# schema.net
KiCad netlist of a schematic drawn in Altium Designer
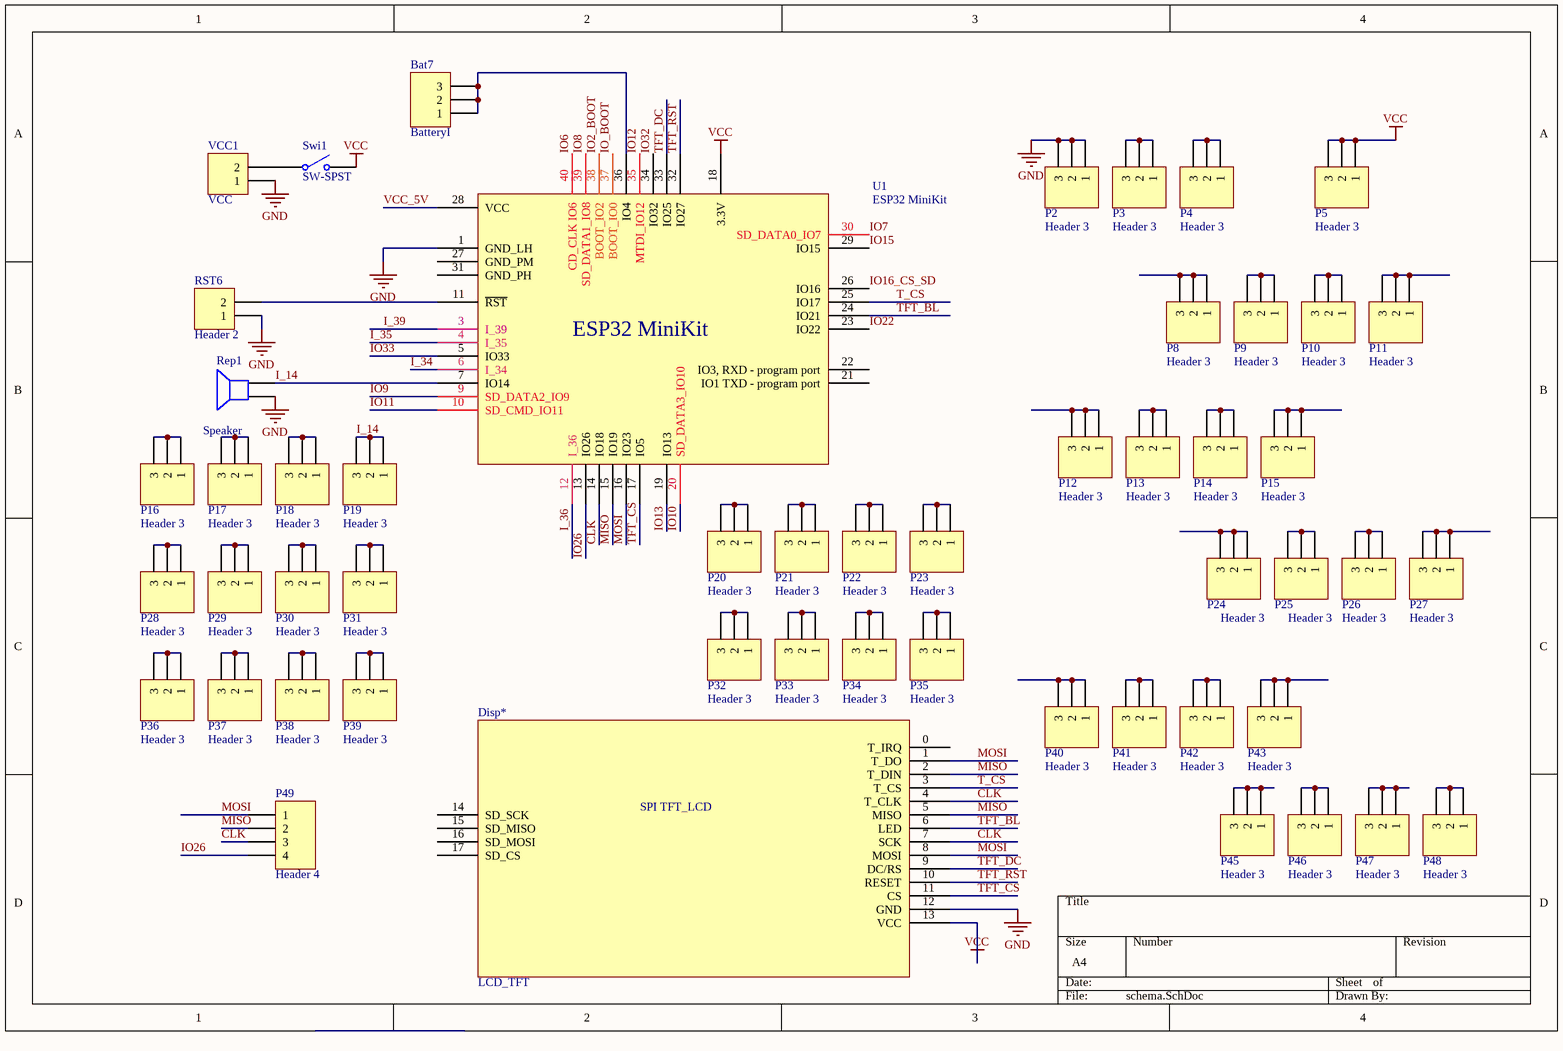
[diagram p0: schema.SchDoc]

(export (version "E")
  (design (tool "Eeschema 10.0.6"))
  (components
    (comp (ref "Bat7")
      (value "BatteryI")
      (footprint "HDR1X3")
      (description "Header, 3-Pin")
      (fields (field (name "PUBLISHER") "Altium Limited"))
      (libsource (lib "") (part "Header 3_1"))
    )
    (comp (ref "Disp*")
      (value "LCD_TFT")
      (footprint "TCT_SPI_480x320 ST7796")
      (libsource (lib "D1_Mini") (part "480x320_tft_SPI_LCD"))
    )
    (comp (ref "P2")
      (value "Header 3")
      (footprint "HDR1X3")
      (description "Header, 3-Pin")
      (fields (field (name "PUBLISHER") "Altium Limited"))
      (libsource (lib "Miscellaneous Connectors") (part "Header 3"))
    )
    (comp (ref "P3")
      (value "Header 3")
      (footprint "HDR1X3")
      (description "Header, 3-Pin")
      (fields (field (name "PUBLISHER") "Altium Limited"))
      (libsource (lib "Miscellaneous Connectors") (part "Header 3"))
    )
    (comp (ref "P4")
      (value "Header 3")
      (footprint "HDR1X3")
      (description "Header, 3-Pin")
      (fields (field (name "PUBLISHER") "Altium Limited"))
      (libsource (lib "Miscellaneous Connectors") (part "Header 3"))
    )
    (comp (ref "P5")
      (value "Header 3")
      (footprint "HDR1X3")
      (description "Header, 3-Pin")
      (fields (field (name "PUBLISHER") "Altium Limited"))
      (libsource (lib "Miscellaneous Connectors") (part "Header 3"))
    )
    (comp (ref "P8")
      (value "Header 3")
      (footprint "HDR1X3")
      (description "Header, 3-Pin")
      (fields (field (name "PUBLISHER") "Altium Limited"))
      (libsource (lib "Miscellaneous Connectors") (part "Header 3"))
    )
    (comp (ref "P9")
      (value "Header 3")
      (footprint "HDR1X3")
      (description "Header, 3-Pin")
      (fields (field (name "PUBLISHER") "Altium Limited"))
      (libsource (lib "Miscellaneous Connectors") (part "Header 3"))
    )
    (comp (ref "P10")
      (value "Header 3")
      (footprint "HDR1X3")
      (description "Header, 3-Pin")
      (fields (field (name "PUBLISHER") "Altium Limited"))
      (libsource (lib "Miscellaneous Connectors") (part "Header 3"))
    )
    (comp (ref "P11")
      (value "Header 3")
      (footprint "HDR1X3")
      (description "Header, 3-Pin")
      (fields (field (name "PUBLISHER") "Altium Limited"))
      (libsource (lib "Miscellaneous Connectors") (part "Header 3"))
    )
    (comp (ref "P12")
      (value "Header 3")
      (footprint "HDR1X3")
      (description "Header, 3-Pin")
      (fields (field (name "PUBLISHER") "Altium Limited"))
      (libsource (lib "Miscellaneous Connectors") (part "Header 3"))
    )
    (comp (ref "P13")
      (value "Header 3")
      (footprint "HDR1X3")
      (description "Header, 3-Pin")
      (fields (field (name "PUBLISHER") "Altium Limited"))
      (libsource (lib "Miscellaneous Connectors") (part "Header 3"))
    )
    (comp (ref "P14")
      (value "Header 3")
      (footprint "HDR1X3")
      (description "Header, 3-Pin")
      (fields (field (name "PUBLISHER") "Altium Limited"))
      (libsource (lib "Miscellaneous Connectors") (part "Header 3"))
    )
    (comp (ref "P15")
      (value "Header 3")
      (footprint "HDR1X3")
      (description "Header, 3-Pin")
      (fields (field (name "PUBLISHER") "Altium Limited"))
      (libsource (lib "Miscellaneous Connectors") (part "Header 3"))
    )
    (comp (ref "P16")
      (value "Header 3")
      (footprint "HDR1X3")
      (description "Header, 3-Pin")
      (fields (field (name "PUBLISHER") "Altium Limited"))
      (libsource (lib "Miscellaneous Connectors") (part "Header 3"))
    )
    (comp (ref "P17")
      (value "Header 3")
      (footprint "HDR1X3")
      (description "Header, 3-Pin")
      (fields (field (name "PUBLISHER") "Altium Limited"))
      (libsource (lib "Miscellaneous Connectors") (part "Header 3"))
    )
    (comp (ref "P18")
      (value "Header 3")
      (footprint "HDR1X3")
      (description "Header, 3-Pin")
      (fields (field (name "PUBLISHER") "Altium Limited"))
      (libsource (lib "Miscellaneous Connectors") (part "Header 3"))
    )
    (comp (ref "P19")
      (value "Header 3")
      (footprint "HDR1X3")
      (description "Header, 3-Pin")
      (fields (field (name "PUBLISHER") "Altium Limited"))
      (libsource (lib "Miscellaneous Connectors") (part "Header 3"))
    )
    (comp (ref "P20")
      (value "Header 3")
      (footprint "HDR1X3")
      (description "Header, 3-Pin")
      (fields (field (name "PUBLISHER") "Altium Limited"))
      (libsource (lib "Miscellaneous Connectors") (part "Header 3"))
    )
    (comp (ref "P21")
      (value "Header 3")
      (footprint "HDR1X3")
      (description "Header, 3-Pin")
      (fields (field (name "PUBLISHER") "Altium Limited"))
      (libsource (lib "Miscellaneous Connectors") (part "Header 3"))
    )
    (comp (ref "P22")
      (value "Header 3")
      (footprint "HDR1X3")
      (description "Header, 3-Pin")
      (fields (field (name "PUBLISHER") "Altium Limited"))
      (libsource (lib "Miscellaneous Connectors") (part "Header 3"))
    )
    (comp (ref "P23")
      (value "Header 3")
      (footprint "HDR1X3")
      (description "Header, 3-Pin")
      (fields (field (name "PUBLISHER") "Altium Limited"))
      (libsource (lib "Miscellaneous Connectors") (part "Header 3"))
    )
    (comp (ref "P24")
      (value "Header 3")
      (footprint "HDR1X3")
      (description "Header, 3-Pin")
      (fields (field (name "PUBLISHER") "Altium Limited"))
      (libsource (lib "Miscellaneous Connectors") (part "Header 3"))
    )
    (comp (ref "P25")
      (value "Header 3")
      (footprint "HDR1X3")
      (description "Header, 3-Pin")
      (fields (field (name "PUBLISHER") "Altium Limited"))
      (libsource (lib "Miscellaneous Connectors") (part "Header 3"))
    )
    (comp (ref "P26")
      (value "Header 3")
      (footprint "HDR1X3")
      (description "Header, 3-Pin")
      (fields (field (name "PUBLISHER") "Altium Limited"))
      (libsource (lib "Miscellaneous Connectors") (part "Header 3"))
    )
    (comp (ref "P27")
      (value "Header 3")
      (footprint "HDR1X3")
      (description "Header, 3-Pin")
      (fields (field (name "PUBLISHER") "Altium Limited"))
      (libsource (lib "Miscellaneous Connectors") (part "Header 3"))
    )
    (comp (ref "P28")
      (value "Header 3")
      (footprint "HDR1X3")
      (description "Header, 3-Pin")
      (fields (field (name "PUBLISHER") "Altium Limited"))
      (libsource (lib "Miscellaneous Connectors") (part "Header 3"))
    )
    (comp (ref "P29")
      (value "Header 3")
      (footprint "HDR1X3")
      (description "Header, 3-Pin")
      (fields (field (name "PUBLISHER") "Altium Limited"))
      (libsource (lib "Miscellaneous Connectors") (part "Header 3"))
    )
    (comp (ref "P30")
      (value "Header 3")
      (footprint "HDR1X3")
      (description "Header, 3-Pin")
      (fields (field (name "PUBLISHER") "Altium Limited"))
      (libsource (lib "Miscellaneous Connectors") (part "Header 3"))
    )
    (comp (ref "P31")
      (value "Header 3")
      (footprint "HDR1X3")
      (description "Header, 3-Pin")
      (fields (field (name "PUBLISHER") "Altium Limited"))
      (libsource (lib "Miscellaneous Connectors") (part "Header 3"))
    )
    (comp (ref "P32")
      (value "Header 3")
      (footprint "HDR1X3")
      (description "Header, 3-Pin")
      (fields (field (name "PUBLISHER") "Altium Limited"))
      (libsource (lib "Miscellaneous Connectors") (part "Header 3"))
    )
    (comp (ref "P33")
      (value "Header 3")
      (footprint "HDR1X3")
      (description "Header, 3-Pin")
      (fields (field (name "PUBLISHER") "Altium Limited"))
      (libsource (lib "Miscellaneous Connectors") (part "Header 3"))
    )
    (comp (ref "P34")
      (value "Header 3")
      (footprint "HDR1X3")
      (description "Header, 3-Pin")
      (fields (field (name "PUBLISHER") "Altium Limited"))
      (libsource (lib "Miscellaneous Connectors") (part "Header 3"))
    )
    (comp (ref "P35")
      (value "Header 3")
      (footprint "HDR1X3")
      (description "Header, 3-Pin")
      (fields (field (name "PUBLISHER") "Altium Limited"))
      (libsource (lib "Miscellaneous Connectors") (part "Header 3"))
    )
    (comp (ref "P36")
      (value "Header 3")
      (footprint "HDR1X3")
      (description "Header, 3-Pin")
      (fields (field (name "PUBLISHER") "Altium Limited"))
      (libsource (lib "Miscellaneous Connectors") (part "Header 3"))
    )
    (comp (ref "P37")
      (value "Header 3")
      (footprint "HDR1X3")
      (description "Header, 3-Pin")
      (fields (field (name "PUBLISHER") "Altium Limited"))
      (libsource (lib "Miscellaneous Connectors") (part "Header 3"))
    )
    (comp (ref "P38")
      (value "Header 3")
      (footprint "HDR1X3")
      (description "Header, 3-Pin")
      (fields (field (name "PUBLISHER") "Altium Limited"))
      (libsource (lib "Miscellaneous Connectors") (part "Header 3"))
    )
    (comp (ref "P39")
      (value "Header 3")
      (footprint "HDR1X3")
      (description "Header, 3-Pin")
      (fields (field (name "PUBLISHER") "Altium Limited"))
      (libsource (lib "Miscellaneous Connectors") (part "Header 3"))
    )
    (comp (ref "P40")
      (value "Header 3")
      (footprint "HDR1X3")
      (description "Header, 3-Pin")
      (fields (field (name "PUBLISHER") "Altium Limited"))
      (libsource (lib "Miscellaneous Connectors") (part "Header 3"))
    )
    (comp (ref "P41")
      (value "Header 3")
      (footprint "HDR1X3")
      (description "Header, 3-Pin")
      (fields (field (name "PUBLISHER") "Altium Limited"))
      (libsource (lib "Miscellaneous Connectors") (part "Header 3"))
    )
    (comp (ref "P42")
      (value "Header 3")
      (footprint "HDR1X3")
      (description "Header, 3-Pin")
      (fields (field (name "PUBLISHER") "Altium Limited"))
      (libsource (lib "Miscellaneous Connectors") (part "Header 3"))
    )
    (comp (ref "P43")
      (value "Header 3")
      (footprint "HDR1X3")
      (description "Header, 3-Pin")
      (fields (field (name "PUBLISHER") "Altium Limited"))
      (libsource (lib "Miscellaneous Connectors") (part "Header 3"))
    )
    (comp (ref "P45")
      (value "Header 3")
      (footprint "HDR1X3")
      (description "Header, 3-Pin")
      (fields (field (name "PUBLISHER") "Altium Limited"))
      (libsource (lib "Miscellaneous Connectors") (part "Header 3"))
    )
    (comp (ref "P46")
      (value "Header 3")
      (footprint "HDR1X3")
      (description "Header, 3-Pin")
      (fields (field (name "PUBLISHER") "Altium Limited"))
      (libsource (lib "Miscellaneous Connectors") (part "Header 3"))
    )
    (comp (ref "P47")
      (value "Header 3")
      (footprint "HDR1X3")
      (description "Header, 3-Pin")
      (fields (field (name "PUBLISHER") "Altium Limited"))
      (libsource (lib "Miscellaneous Connectors") (part "Header 3"))
    )
    (comp (ref "P48")
      (value "Header 3")
      (footprint "HDR1X3")
      (description "Header, 3-Pin")
      (fields (field (name "PUBLISHER") "Altium Limited"))
      (libsource (lib "Miscellaneous Connectors") (part "Header 3"))
    )
    (comp (ref "P49")
      (value "Header 4")
      (footprint "HDR1X4")
      (description "Header, 4-Pin")
      (fields (field (name "PUBLISHER") "Altium Limited"))
      (libsource (lib "Miscellaneous Connectors") (part "Header 4"))
    )
    (comp (ref "Rep1")
      (value "Speaker")
      (footprint "PIN2")
      (description "Loudspeaker")
      (fields (field (name "PUBLISHER") "Altium Limited"))
      (libsource (lib "Miscellaneous Devices") (part "Speaker"))
    )
    (comp (ref "RST6")
      (value "Header 2")
      (footprint "HDR1X2")
      (description "Header, 2-Pin")
      (fields (field (name "PUBLISHER") "Altium Limited"))
      (libsource (lib "Miscellaneous Connectors") (part "Header 2"))
    )
    (comp (ref "Swi1")
      (value "SW-SPST")
      (footprint "SPST-2")
      (description "Single-Pole, Single-Throw Switch")
      (fields (field (name "PUBLISHER") "Altium Limited"))
      (libsource (lib "Miscellaneous Devices") (part "SW-SPST"))
    )
    (comp (ref "U1")
      (value "ESP32 MiniKit")
      (footprint "esp32")
      (libsource (lib "D1_Mini") (part "ESP32 Wemos"))
    )
    (comp (ref "VCC1")
      (value "VCC")
      (footprint "HDR1X2")
      (description "Header, 2-Pin")
      (fields (field (name "PUBLISHER") "Altium Limited"))
      (libsource (lib "Miscellaneous Connectors") (part "Header 2"))
    )
  )
  (nets
    (net (code "1") (name "/CLK") (class "Default")
      (node (ref "Disp*") (pin "4") (pinfunction "T_CLK_4") (pintype "passive"))
      (node (ref "Disp*") (pin "7") (pinfunction "SCK_7") (pintype "passive"))
      (node (ref "P49") (pin "3") (pinfunction "3_3") (pintype "passive"))
      (node (ref "U1") (pin "14") (pinfunction "IO18_14") (pintype "passive"))
    )
    (net (code "2") (name "/IO2_BOOT") (class "Default")
      (node (ref "U1") (pin "38") (pinfunction "BOOT_IO2_38") (pintype "passive"))
    )
    (net (code "3") (name "/IO6") (class "Default")
      (node (ref "U1") (pin "40") (pinfunction "CD_CLK_IO6_40") (pintype "passive"))
    )
    (net (code "4") (name "/IO7") (class "Default")
      (node (ref "U1") (pin "30") (pinfunction "SD_DATA0_IO7_30") (pintype "passive"))
    )
    (net (code "5") (name "/IO8") (class "Default")
      (node (ref "U1") (pin "39") (pinfunction "SD_DATA1_IO8_39") (pintype "passive"))
    )
    (net (code "6") (name "/IO9") (class "Default")
      (node (ref "U1") (pin "9") (pinfunction "SD_DATA2_IO9_9") (pintype "passive"))
    )
    (net (code "7") (name "/IO10") (class "Default")
      (node (ref "U1") (pin "20") (pinfunction "SD_DATA3_IO10_20") (pintype "passive"))
    )
    (net (code "8") (name "/IO11") (class "Default")
      (node (ref "U1") (pin "10") (pinfunction "SD_CMD_IO11_10") (pintype "passive"))
    )
    (net (code "9") (name "/IO12") (class "Default")
      (node (ref "U1") (pin "35") (pinfunction "MTDI_IO12_35") (pintype "passive"))
    )
    (net (code "10") (name "/IO13") (class "Default")
      (node (ref "U1") (pin "19") (pinfunction "IO13_19") (pintype "passive"))
    )
    (net (code "11") (name "/IO15") (class "Default")
      (node (ref "U1") (pin "29") (pinfunction "IO15_29") (pintype "passive"))
    )
    (net (code "12") (name "/IO16_CS_SD") (class "Default")
      (node (ref "U1") (pin "26") (pinfunction "IO16_26") (pintype "passive"))
    )
    (net (code "13") (name "/IO22") (class "Default")
      (node (ref "U1") (pin "23") (pinfunction "IO22_23") (pintype "passive"))
    )
    (net (code "14") (name "/IO26") (class "Default")
      (node (ref "P49") (pin "4") (pinfunction "4_4") (pintype "passive"))
      (node (ref "U1") (pin "13") (pinfunction "IO26_13") (pintype "passive"))
    )
    (net (code "15") (name "/IO32") (class "Default")
      (node (ref "U1") (pin "34") (pinfunction "IO32_34") (pintype "passive"))
    )
    (net (code "16") (name "/IO33") (class "Default")
      (node (ref "U1") (pin "5") (pinfunction "IO33_5") (pintype "passive"))
    )
    (net (code "17") (name "/IO_BOOT") (class "Default")
      (node (ref "U1") (pin "37") (pinfunction "BOOT_IO0_37") (pintype "passive"))
    )
    (net (code "18") (name "/I_14") (class "Default")
      (node (ref "P19") (pin "1") (pinfunction "1_1") (pintype "passive"))
      (node (ref "P19") (pin "2") (pinfunction "2_2") (pintype "passive"))
      (node (ref "P19") (pin "3") (pinfunction "3_3") (pintype "passive"))
      (node (ref "Rep1") (pin "2") (pinfunction "2_2") (pintype "passive"))
      (node (ref "U1") (pin "7") (pinfunction "IO14_7") (pintype "passive"))
    )
    (net (code "19") (name "/I_34") (class "Default")
      (node (ref "U1") (pin "6") (pinfunction "I_34_6") (pintype "passive"))
    )
    (net (code "20") (name "/I_35") (class "Default")
      (node (ref "U1") (pin "4") (pinfunction "I_35_4") (pintype "passive"))
    )
    (net (code "21") (name "/I_36") (class "Default")
      (node (ref "U1") (pin "12") (pinfunction "I_36_12") (pintype "passive"))
    )
    (net (code "22") (name "/I_39") (class "Default")
      (node (ref "U1") (pin "3") (pinfunction "I_39_3") (pintype "passive"))
    )
    (net (code "23") (name "/MISO") (class "Default")
      (node (ref "Disp*") (pin "2") (pinfunction "T_DIN_2") (pintype "passive"))
      (node (ref "Disp*") (pin "5") (pinfunction "MISO_5") (pintype "passive"))
      (node (ref "P49") (pin "2") (pinfunction "2_2") (pintype "passive"))
      (node (ref "U1") (pin "15") (pinfunction "IO19_15") (pintype "passive"))
    )
    (net (code "24") (name "/MOSI") (class "Default")
      (node (ref "Disp*") (pin "1") (pinfunction "T_DO_1") (pintype "passive"))
      (node (ref "Disp*") (pin "8") (pinfunction "MOSI_8") (pintype "passive"))
      (node (ref "P49") (pin "1") (pinfunction "1_1") (pintype "passive"))
      (node (ref "U1") (pin "16") (pinfunction "IO23_16") (pintype "passive"))
    )
    (net (code "25") (name "/TFT_BL") (class "Default")
      (node (ref "Disp*") (pin "6") (pinfunction "LED_6") (pintype "passive"))
      (node (ref "U1") (pin "24") (pinfunction "IO21_24") (pintype "passive"))
    )
    (net (code "26") (name "/TFT_CS") (class "Default")
      (node (ref "Disp*") (pin "11") (pinfunction "CS_11") (pintype "passive"))
      (node (ref "U1") (pin "17") (pinfunction "IO5_17") (pintype "passive"))
    )
    (net (code "27") (name "/TFT_DC") (class "Default")
      (node (ref "Disp*") (pin "9") (pinfunction "DC/RS_9") (pintype "passive"))
      (node (ref "U1") (pin "33") (pinfunction "IO25_33") (pintype "passive"))
    )
    (net (code "28") (name "/TFT_RST") (class "Default")
      (node (ref "Disp*") (pin "10") (pinfunction "RESET_10") (pintype "passive"))
      (node (ref "U1") (pin "32") (pinfunction "IO27_32") (pintype "passive"))
    )
    (net (code "29") (name "/T_CS") (class "Default")
      (node (ref "Disp*") (pin "3") (pinfunction "T_CS_3") (pintype "passive"))
      (node (ref "U1") (pin "25") (pinfunction "IO17_25") (pintype "passive"))
    )
    (net (code "30") (name "/VCC_5V") (class "Default")
      (node (ref "U1") (pin "28") (pinfunction "VCC_28") (pintype "passive"))
    )
    (net (code "31") (name "GND") (class "Default")
      (node (ref "Disp*") (pin "12") (pinfunction "GND_12") (pintype "passive"))
      (node (ref "P2") (pin "1") (pinfunction "1_1") (pintype "passive"))
      (node (ref "P2") (pin "2") (pinfunction "2_2") (pintype "passive"))
      (node (ref "P2") (pin "3") (pinfunction "3_3") (pintype "passive"))
      (node (ref "RST6") (pin "1") (pinfunction "1_1") (pintype "passive"))
      (node (ref "Rep1") (pin "1") (pinfunction "1_1") (pintype "passive"))
      (node (ref "U1") (pin "1") (pinfunction "GND_LH_1") (pintype "power_in"))
      (node (ref "VCC1") (pin "1") (pinfunction "1_1") (pintype "passive"))
    )
    (net (code "32") (name "Net-(P3-Pad1)") (class "Default")
      (node (ref "P3") (pin "1") (pinfunction "1_1") (pintype "passive"))
      (node (ref "P3") (pin "2") (pinfunction "2_2") (pintype "passive"))
      (node (ref "P3") (pin "3") (pinfunction "3_3") (pintype "passive"))
    )
    (net (code "33") (name "Net-(P4-Pad1)") (class "Default")
      (node (ref "P4") (pin "1") (pinfunction "1_1") (pintype "passive"))
      (node (ref "P4") (pin "2") (pinfunction "2_2") (pintype "passive"))
      (node (ref "P4") (pin "3") (pinfunction "3_3") (pintype "passive"))
    )
    (net (code "34") (name "Net-(P8-Pad1)") (class "Default")
      (node (ref "P8") (pin "1") (pinfunction "1_1") (pintype "passive"))
      (node (ref "P8") (pin "2") (pinfunction "2_2") (pintype "passive"))
      (node (ref "P8") (pin "3") (pinfunction "3_3") (pintype "passive"))
    )
    (net (code "35") (name "Net-(P9-Pad1)") (class "Default")
      (node (ref "P9") (pin "1") (pinfunction "1_1") (pintype "passive"))
      (node (ref "P9") (pin "2") (pinfunction "2_2") (pintype "passive"))
      (node (ref "P9") (pin "3") (pinfunction "3_3") (pintype "passive"))
    )
    (net (code "36") (name "Net-(P10-Pad1)") (class "Default")
      (node (ref "P10") (pin "1") (pinfunction "1_1") (pintype "passive"))
      (node (ref "P10") (pin "2") (pinfunction "2_2") (pintype "passive"))
      (node (ref "P10") (pin "3") (pinfunction "3_3") (pintype "passive"))
    )
    (net (code "37") (name "Net-(P11-Pad1)") (class "Default")
      (node (ref "P11") (pin "1") (pinfunction "1_1") (pintype "passive"))
      (node (ref "P11") (pin "2") (pinfunction "2_2") (pintype "passive"))
      (node (ref "P11") (pin "3") (pinfunction "3_3") (pintype "passive"))
    )
    (net (code "38") (name "Net-(P12-Pad1)") (class "Default")
      (node (ref "P12") (pin "1") (pinfunction "1_1") (pintype "passive"))
      (node (ref "P12") (pin "2") (pinfunction "2_2") (pintype "passive"))
      (node (ref "P12") (pin "3") (pinfunction "3_3") (pintype "passive"))
    )
    (net (code "39") (name "Net-(P13-Pad1)") (class "Default")
      (node (ref "P13") (pin "1") (pinfunction "1_1") (pintype "passive"))
      (node (ref "P13") (pin "2") (pinfunction "2_2") (pintype "passive"))
      (node (ref "P13") (pin "3") (pinfunction "3_3") (pintype "passive"))
    )
    (net (code "40") (name "Net-(P14-Pad1)") (class "Default")
      (node (ref "P14") (pin "1") (pinfunction "1_1") (pintype "passive"))
      (node (ref "P14") (pin "2") (pinfunction "2_2") (pintype "passive"))
      (node (ref "P14") (pin "3") (pinfunction "3_3") (pintype "passive"))
    )
    (net (code "41") (name "Net-(P15-Pad1)") (class "Default")
      (node (ref "P15") (pin "1") (pinfunction "1_1") (pintype "passive"))
      (node (ref "P15") (pin "2") (pinfunction "2_2") (pintype "passive"))
      (node (ref "P15") (pin "3") (pinfunction "3_3") (pintype "passive"))
    )
    (net (code "42") (name "Net-(P16-Pad1)") (class "Default")
      (node (ref "P16") (pin "1") (pinfunction "1_1") (pintype "passive"))
      (node (ref "P16") (pin "2") (pinfunction "2_2") (pintype "passive"))
      (node (ref "P16") (pin "3") (pinfunction "3_3") (pintype "passive"))
    )
    (net (code "43") (name "Net-(P17-Pad1)") (class "Default")
      (node (ref "P17") (pin "1") (pinfunction "1_1") (pintype "passive"))
      (node (ref "P17") (pin "2") (pinfunction "2_2") (pintype "passive"))
      (node (ref "P17") (pin "3") (pinfunction "3_3") (pintype "passive"))
    )
    (net (code "44") (name "Net-(P18-Pad1)") (class "Default")
      (node (ref "P18") (pin "1") (pinfunction "1_1") (pintype "passive"))
      (node (ref "P18") (pin "2") (pinfunction "2_2") (pintype "passive"))
      (node (ref "P18") (pin "3") (pinfunction "3_3") (pintype "passive"))
    )
    (net (code "45") (name "Net-(P20-Pad1)") (class "Default")
      (node (ref "P20") (pin "1") (pinfunction "1_1") (pintype "passive"))
      (node (ref "P20") (pin "2") (pinfunction "2_2") (pintype "passive"))
      (node (ref "P20") (pin "3") (pinfunction "3_3") (pintype "passive"))
    )
    (net (code "46") (name "Net-(P21-Pad1)") (class "Default")
      (node (ref "P21") (pin "1") (pinfunction "1_1") (pintype "passive"))
      (node (ref "P21") (pin "2") (pinfunction "2_2") (pintype "passive"))
      (node (ref "P21") (pin "3") (pinfunction "3_3") (pintype "passive"))
    )
    (net (code "47") (name "Net-(P22-Pad1)") (class "Default")
      (node (ref "P22") (pin "1") (pinfunction "1_1") (pintype "passive"))
      (node (ref "P22") (pin "2") (pinfunction "2_2") (pintype "passive"))
      (node (ref "P22") (pin "3") (pinfunction "3_3") (pintype "passive"))
    )
    (net (code "48") (name "Net-(P23-Pad1)") (class "Default")
      (node (ref "P23") (pin "1") (pinfunction "1_1") (pintype "passive"))
      (node (ref "P23") (pin "2") (pinfunction "2_2") (pintype "passive"))
      (node (ref "P23") (pin "3") (pinfunction "3_3") (pintype "passive"))
    )
    (net (code "49") (name "Net-(P24-Pad1)") (class "Default")
      (node (ref "P24") (pin "1") (pinfunction "1_1") (pintype "passive"))
      (node (ref "P24") (pin "2") (pinfunction "2_2") (pintype "passive"))
      (node (ref "P24") (pin "3") (pinfunction "3_3") (pintype "passive"))
    )
    (net (code "50") (name "Net-(P25-Pad1)") (class "Default")
      (node (ref "P25") (pin "1") (pinfunction "1_1") (pintype "passive"))
      (node (ref "P25") (pin "2") (pinfunction "2_2") (pintype "passive"))
      (node (ref "P25") (pin "3") (pinfunction "3_3") (pintype "passive"))
    )
    (net (code "51") (name "Net-(P26-Pad1)") (class "Default")
      (node (ref "P26") (pin "1") (pinfunction "1_1") (pintype "passive"))
      (node (ref "P26") (pin "2") (pinfunction "2_2") (pintype "passive"))
      (node (ref "P26") (pin "3") (pinfunction "3_3") (pintype "passive"))
    )
    (net (code "52") (name "Net-(P27-Pad1)") (class "Default")
      (node (ref "P27") (pin "1") (pinfunction "1_1") (pintype "passive"))
      (node (ref "P27") (pin "2") (pinfunction "2_2") (pintype "passive"))
      (node (ref "P27") (pin "3") (pinfunction "3_3") (pintype "passive"))
    )
    (net (code "53") (name "Net-(P28-Pad1)") (class "Default")
      (node (ref "P28") (pin "1") (pinfunction "1_1") (pintype "passive"))
      (node (ref "P28") (pin "2") (pinfunction "2_2") (pintype "passive"))
      (node (ref "P28") (pin "3") (pinfunction "3_3") (pintype "passive"))
    )
    (net (code "54") (name "Net-(P29-Pad1)") (class "Default")
      (node (ref "P29") (pin "1") (pinfunction "1_1") (pintype "passive"))
      (node (ref "P29") (pin "2") (pinfunction "2_2") (pintype "passive"))
      (node (ref "P29") (pin "3") (pinfunction "3_3") (pintype "passive"))
    )
    (net (code "55") (name "Net-(P30-Pad1)") (class "Default")
      (node (ref "P30") (pin "1") (pinfunction "1_1") (pintype "passive"))
      (node (ref "P30") (pin "2") (pinfunction "2_2") (pintype "passive"))
      (node (ref "P30") (pin "3") (pinfunction "3_3") (pintype "passive"))
    )
    (net (code "56") (name "Net-(P31-Pad1)") (class "Default")
      (node (ref "P31") (pin "1") (pinfunction "1_1") (pintype "passive"))
      (node (ref "P31") (pin "2") (pinfunction "2_2") (pintype "passive"))
      (node (ref "P31") (pin "3") (pinfunction "3_3") (pintype "passive"))
    )
    (net (code "57") (name "Net-(P32-Pad1)") (class "Default")
      (node (ref "P32") (pin "1") (pinfunction "1_1") (pintype "passive"))
      (node (ref "P32") (pin "2") (pinfunction "2_2") (pintype "passive"))
      (node (ref "P32") (pin "3") (pinfunction "3_3") (pintype "passive"))
    )
    (net (code "58") (name "Net-(P33-Pad1)") (class "Default")
      (node (ref "P33") (pin "1") (pinfunction "1_1") (pintype "passive"))
      (node (ref "P33") (pin "2") (pinfunction "2_2") (pintype "passive"))
      (node (ref "P33") (pin "3") (pinfunction "3_3") (pintype "passive"))
    )
    (net (code "59") (name "Net-(P34-Pad1)") (class "Default")
      (node (ref "P34") (pin "1") (pinfunction "1_1") (pintype "passive"))
      (node (ref "P34") (pin "2") (pinfunction "2_2") (pintype "passive"))
      (node (ref "P34") (pin "3") (pinfunction "3_3") (pintype "passive"))
    )
    (net (code "60") (name "Net-(P35-Pad1)") (class "Default")
      (node (ref "P35") (pin "1") (pinfunction "1_1") (pintype "passive"))
      (node (ref "P35") (pin "2") (pinfunction "2_2") (pintype "passive"))
      (node (ref "P35") (pin "3") (pinfunction "3_3") (pintype "passive"))
    )
    (net (code "61") (name "Net-(P36-Pad1)") (class "Default")
      (node (ref "P36") (pin "1") (pinfunction "1_1") (pintype "passive"))
      (node (ref "P36") (pin "2") (pinfunction "2_2") (pintype "passive"))
      (node (ref "P36") (pin "3") (pinfunction "3_3") (pintype "passive"))
    )
    (net (code "62") (name "Net-(P37-Pad1)") (class "Default")
      (node (ref "P37") (pin "1") (pinfunction "1_1") (pintype "passive"))
      (node (ref "P37") (pin "2") (pinfunction "2_2") (pintype "passive"))
      (node (ref "P37") (pin "3") (pinfunction "3_3") (pintype "passive"))
    )
    (net (code "63") (name "Net-(P38-Pad1)") (class "Default")
      (node (ref "P38") (pin "1") (pinfunction "1_1") (pintype "passive"))
      (node (ref "P38") (pin "2") (pinfunction "2_2") (pintype "passive"))
      (node (ref "P38") (pin "3") (pinfunction "3_3") (pintype "passive"))
    )
    (net (code "64") (name "Net-(P39-Pad1)") (class "Default")
      (node (ref "P39") (pin "1") (pinfunction "1_1") (pintype "passive"))
      (node (ref "P39") (pin "2") (pinfunction "2_2") (pintype "passive"))
      (node (ref "P39") (pin "3") (pinfunction "3_3") (pintype "passive"))
    )
    (net (code "65") (name "Net-(P40-Pad1)") (class "Default")
      (node (ref "P40") (pin "1") (pinfunction "1_1") (pintype "passive"))
      (node (ref "P40") (pin "2") (pinfunction "2_2") (pintype "passive"))
      (node (ref "P40") (pin "3") (pinfunction "3_3") (pintype "passive"))
    )
    (net (code "66") (name "Net-(P41-Pad1)") (class "Default")
      (node (ref "P41") (pin "1") (pinfunction "1_1") (pintype "passive"))
      (node (ref "P41") (pin "2") (pinfunction "2_2") (pintype "passive"))
      (node (ref "P41") (pin "3") (pinfunction "3_3") (pintype "passive"))
    )
    (net (code "67") (name "Net-(P42-Pad1)") (class "Default")
      (node (ref "P42") (pin "1") (pinfunction "1_1") (pintype "passive"))
      (node (ref "P42") (pin "2") (pinfunction "2_2") (pintype "passive"))
      (node (ref "P42") (pin "3") (pinfunction "3_3") (pintype "passive"))
    )
    (net (code "68") (name "Net-(P43-Pad1)") (class "Default")
      (node (ref "P43") (pin "1") (pinfunction "1_1") (pintype "passive"))
      (node (ref "P43") (pin "2") (pinfunction "2_2") (pintype "passive"))
      (node (ref "P43") (pin "3") (pinfunction "3_3") (pintype "passive"))
    )
    (net (code "69") (name "Net-(P45-Pad1)") (class "Default")
      (node (ref "P45") (pin "1") (pinfunction "1_1") (pintype "passive"))
      (node (ref "P45") (pin "2") (pinfunction "2_2") (pintype "passive"))
      (node (ref "P45") (pin "3") (pinfunction "3_3") (pintype "passive"))
    )
    (net (code "70") (name "Net-(P46-Pad1)") (class "Default")
      (node (ref "P46") (pin "1") (pinfunction "1_1") (pintype "passive"))
      (node (ref "P46") (pin "2") (pinfunction "2_2") (pintype "passive"))
      (node (ref "P46") (pin "3") (pinfunction "3_3") (pintype "passive"))
    )
    (net (code "71") (name "Net-(P47-Pad1)") (class "Default")
      (node (ref "P47") (pin "1") (pinfunction "1_1") (pintype "passive"))
      (node (ref "P47") (pin "2") (pinfunction "2_2") (pintype "passive"))
      (node (ref "P47") (pin "3") (pinfunction "3_3") (pintype "passive"))
    )
    (net (code "72") (name "Net-(P48-Pad1)") (class "Default")
      (node (ref "P48") (pin "1") (pinfunction "1_1") (pintype "passive"))
      (node (ref "P48") (pin "2") (pinfunction "2_2") (pintype "passive"))
      (node (ref "P48") (pin "3") (pinfunction "3_3") (pintype "passive"))
    )
    (net (code "73") (name "Net-(Swi1-COMMON)") (class "Default")
      (node (ref "Swi1") (pin "1") (pinfunction "COMMON_1") (pintype "passive"))
      (node (ref "VCC1") (pin "2") (pinfunction "2_2") (pintype "passive"))
    )
    (net (code "74") (name "Net-(U1-IO4)") (class "Default")
      (node (ref "Bat7") (pin "1") (pinfunction "1_1") (pintype "passive"))
      (node (ref "Bat7") (pin "2") (pinfunction "2_2") (pintype "passive"))
      (node (ref "Bat7") (pin "3") (pinfunction "3_3") (pintype "passive"))
      (node (ref "U1") (pin "36") (pinfunction "IO4_36") (pintype "passive"))
    )
    (net (code "75") (name "Net-(U1-~{RST})") (class "Default")
      (node (ref "RST6") (pin "2") (pinfunction "2_2") (pintype "passive"))
      (node (ref "U1") (pin "11") (pinfunction "~{RST}_11") (pintype "passive"))
    )
    (net (code "76") (name "VCC") (class "Default")
      (node (ref "Disp*") (pin "13") (pinfunction "VCC_13") (pintype "passive"))
      (node (ref "P5") (pin "1") (pinfunction "1_1") (pintype "passive"))
      (node (ref "P5") (pin "2") (pinfunction "2_2") (pintype "passive"))
      (node (ref "P5") (pin "3") (pinfunction "3_3") (pintype "passive"))
      (node (ref "Swi1") (pin "2") (pinfunction "NO_2") (pintype "passive"))
      (node (ref "U1") (pin "18") (pinfunction "3.3V_18") (pintype "passive"))
    )
    (net (code "77") (name "unconnected-(Disp*-SD_CS-Pad17)") (class "Default")
      (node (ref "Disp*") (pin "17") (pinfunction "SD_CS_17") (pintype "passive"))
    )
    (net (code "78") (name "unconnected-(Disp*-SD_MISO-Pad15)") (class "Default")
      (node (ref "Disp*") (pin "15") (pinfunction "SD_MISO_15") (pintype "passive"))
    )
    (net (code "79") (name "unconnected-(Disp*-SD_MOSI-Pad16)") (class "Default")
      (node (ref "Disp*") (pin "16") (pinfunction "SD_MOSI_16") (pintype "passive"))
    )
    (net (code "80") (name "unconnected-(Disp*-SD_SCK-Pad14)") (class "Default")
      (node (ref "Disp*") (pin "14") (pinfunction "SD_SCK_14") (pintype "passive"))
    )
    (net (code "81") (name "unconnected-(Disp*-T_IRQ-Pad0)") (class "Default")
      (node (ref "Disp*") (pin "0") (pinfunction "T_IRQ_0") (pintype "passive"))
    )
    (net (code "82") (name "unconnected-(U1-GND_PH-Pad31)") (class "Default")
      (node (ref "U1") (pin "31") (pinfunction "GND_PH_31") (pintype "passive"))
    )
    (net (code "83") (name "unconnected-(U1-GND_PM-Pad27)") (class "Default")
      (node (ref "U1") (pin "27") (pinfunction "GND_PM_27") (pintype "passive"))
    )
    (net (code "84") (name "unconnected-(U1-IO1_TXD_-_program_port-Pad21)") (class "Default")
      (node (ref "U1") (pin "21") (pinfunction "IO1_TXD_-_program_port_21") (pintype "passive"))
    )
    (net (code "85") (name "unconnected-(U1-IO3,_RXD_-_program_port-Pad22)") (class "Default")
      (node (ref "U1") (pin "22") (pinfunction "IO3,_RXD_-_program_port_22") (pintype "passive"))
    )
    (net (code "86") (name "unconnected-(U1-NC-Pad2)") (class "Default")
      (node (ref "U1") (pin "2") (pinfunction "NC_2") (pintype "passive"))
    )
    (net (code "87") (name "unconnected-(U1-NC-Pad8)") (class "Default")
      (node (ref "U1") (pin "8") (pinfunction "NC_8") (pintype "passive"))
    )
  )
)
